# grbl-shield-easydriver.net
KiCad netlist of a schematic drawn in EAGLE
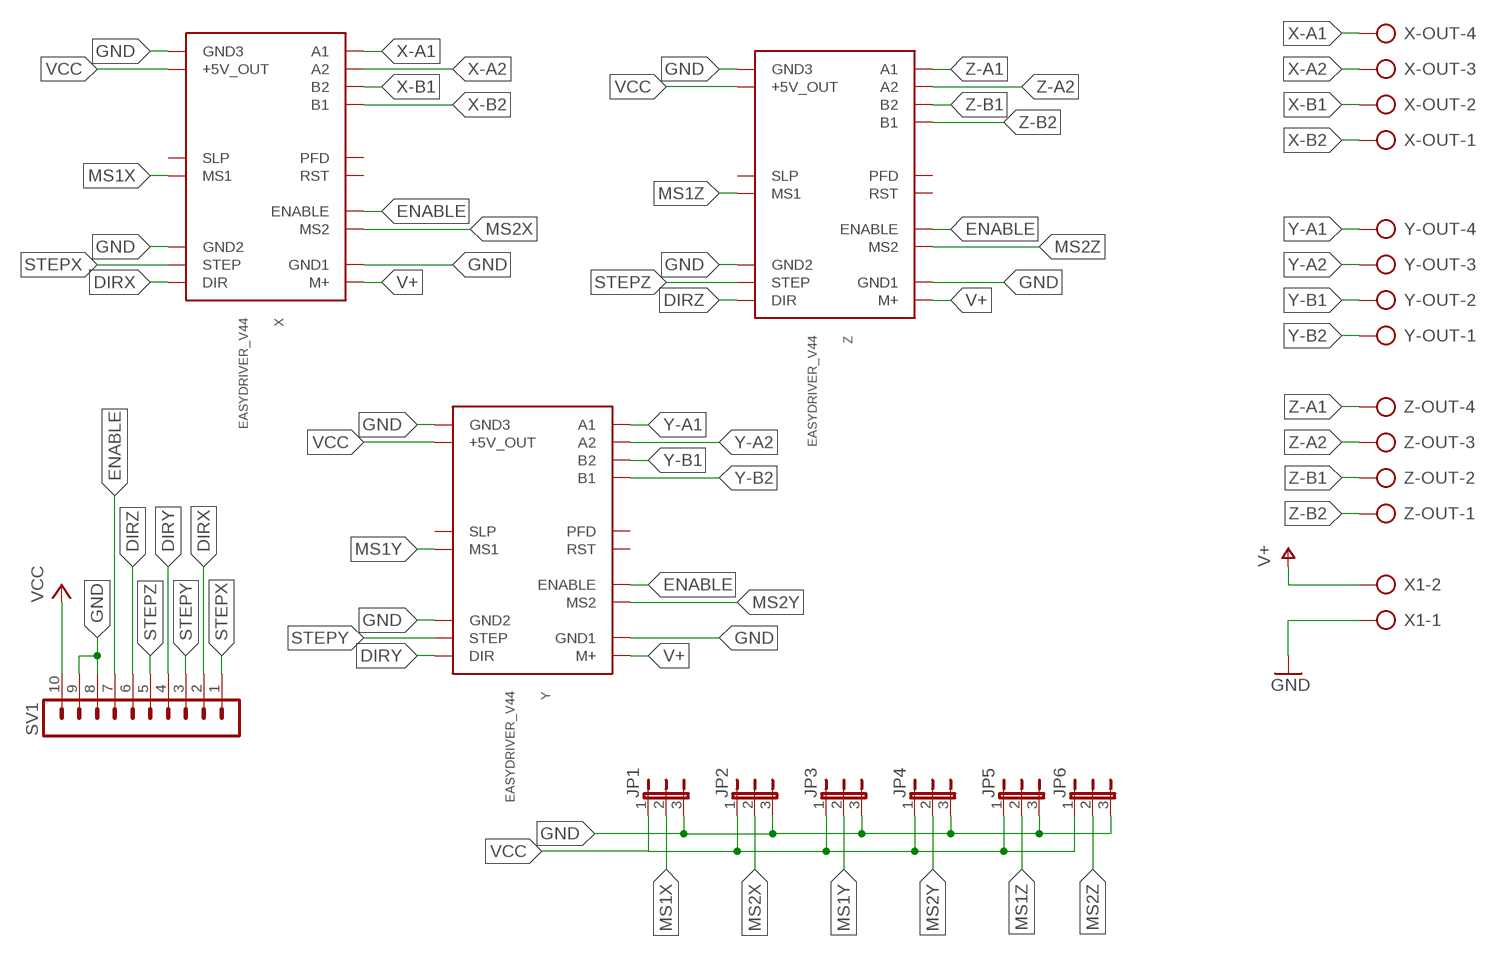
[diagram p0: schematic, sheet 1]

(export (version "E")
  (design (tool "Eeschema 10.0.6"))
  (components
    (comp (ref "JP1")
      (value "JP2E")
      (footprint "eagle-import:JP2")
      (libsource (lib "eagle-import") (part "JP2E"))
    )
    (comp (ref "JP2")
      (value "JP2E")
      (footprint "eagle-import:JP2")
      (libsource (lib "eagle-import") (part "JP2E"))
    )
    (comp (ref "JP3")
      (value "JP2E")
      (footprint "eagle-import:JP2")
      (libsource (lib "eagle-import") (part "JP2E"))
    )
    (comp (ref "JP4")
      (value "JP2E")
      (footprint "eagle-import:JP2")
      (libsource (lib "eagle-import") (part "JP2E"))
    )
    (comp (ref "JP5")
      (value "JP2E")
      (footprint "eagle-import:JP2")
      (libsource (lib "eagle-import") (part "JP2E"))
    )
    (comp (ref "JP6")
      (value "JP2E")
      (footprint "eagle-import:JP2")
      (libsource (lib "eagle-import") (part "JP2E"))
    )
    (comp (ref "SV1")
      (value "MA10-1")
      (footprint "eagle-import:MA10-1")
      (libsource (lib "eagle-import") (part "MA10-1"))
    )
    (comp (ref "X")
      (value "EASYDRIVER_V44")
      (footprint "eagle-import:EASYDRIVER_V44")
      (libsource (lib "eagle-import") (part "EASYDRIVER_V44"))
    )
    (comp (ref "X-OUT")
      (value "AK500/4")
      (footprint "eagle-import:AK500_4")
      (libsource (lib "eagle-import") (part "AK500/4"))
    )
    (comp (ref "X1")
      (value "AK500/2")
      (footprint "eagle-import:AK500_2")
      (libsource (lib "eagle-import") (part "AK500/2"))
    )
    (comp (ref "Y")
      (value "EASYDRIVER_V44")
      (footprint "eagle-import:EASYDRIVER_V44")
      (libsource (lib "eagle-import") (part "EASYDRIVER_V44"))
    )
    (comp (ref "Y-OUT")
      (value "AK500/4")
      (footprint "eagle-import:AK500_4")
      (libsource (lib "eagle-import") (part "AK500/4"))
    )
    (comp (ref "Z")
      (value "EASYDRIVER_V44")
      (footprint "eagle-import:EASYDRIVER_V44")
      (libsource (lib "eagle-import") (part "EASYDRIVER_V44"))
    )
    (comp (ref "Z-OUT")
      (value "AK500/4")
      (footprint "eagle-import:AK500_4")
      (libsource (lib "eagle-import") (part "AK500/4"))
    )
  )
  (nets
    (net (code "1") (name "DIRX") (class "Default")
      (node (ref "SV1") (pin "2") (pinfunction "2_2") (pintype "passive"))
      (node (ref "X") (pin "DIR") (pinfunction "DIR_DIR") (pintype "bidirectional"))
    )
    (net (code "2") (name "DIRY") (class "Default")
      (node (ref "SV1") (pin "4") (pinfunction "4_4") (pintype "passive"))
      (node (ref "Y") (pin "DIR") (pinfunction "DIR_DIR") (pintype "bidirectional"))
    )
    (net (code "3") (name "DIRZ") (class "Default")
      (node (ref "SV1") (pin "6") (pinfunction "6_6") (pintype "passive"))
      (node (ref "Z") (pin "DIR") (pinfunction "DIR_DIR") (pintype "bidirectional"))
    )
    (net (code "4") (name "ENABLE") (class "Default")
      (node (ref "SV1") (pin "7") (pinfunction "7_7") (pintype "passive"))
      (node (ref "X") (pin "ENABLE") (pinfunction "ENABLE_ENABLE") (pintype "bidirectional"))
      (node (ref "Y") (pin "ENABLE") (pinfunction "ENABLE_ENABLE") (pintype "bidirectional"))
      (node (ref "Z") (pin "ENABLE") (pinfunction "ENABLE_ENABLE") (pintype "bidirectional"))
    )
    (net (code "5") (name "GND") (class "Default")
      (node (ref "JP1") (pin "3") (pinfunction "3_3") (pintype "passive"))
      (node (ref "JP2") (pin "3") (pinfunction "3_3") (pintype "passive"))
      (node (ref "JP3") (pin "3") (pinfunction "3_3") (pintype "passive"))
      (node (ref "JP4") (pin "3") (pinfunction "3_3") (pintype "passive"))
      (node (ref "JP5") (pin "3") (pinfunction "3_3") (pintype "passive"))
      (node (ref "JP6") (pin "3") (pinfunction "3_3") (pintype "passive"))
      (node (ref "SV1") (pin "8") (pinfunction "8_8") (pintype "passive"))
      (node (ref "SV1") (pin "9") (pinfunction "9_9") (pintype "passive"))
      (node (ref "X") (pin "GND1") (pinfunction "GND1_GND1") (pintype "bidirectional"))
      (node (ref "X") (pin "GND2") (pinfunction "GND2_GND2") (pintype "bidirectional"))
      (node (ref "X") (pin "GND3") (pinfunction "GND3_GND3") (pintype "bidirectional"))
      (node (ref "X1") (pin "1") (pinfunction "KL_1") (pintype "passive"))
      (node (ref "Y") (pin "GND1") (pinfunction "GND1_GND1") (pintype "bidirectional"))
      (node (ref "Y") (pin "GND2") (pinfunction "GND2_GND2") (pintype "bidirectional"))
      (node (ref "Y") (pin "GND3") (pinfunction "GND3_GND3") (pintype "bidirectional"))
      (node (ref "Z") (pin "GND1") (pinfunction "GND1_GND1") (pintype "bidirectional"))
      (node (ref "Z") (pin "GND2") (pinfunction "GND2_GND2") (pintype "bidirectional"))
      (node (ref "Z") (pin "GND3") (pinfunction "GND3_GND3") (pintype "bidirectional"))
    )
    (net (code "6") (name "MS1X") (class "Default")
      (node (ref "JP1") (pin "2") (pinfunction "2_2") (pintype "passive"))
      (node (ref "X") (pin "MS1") (pinfunction "MS1_MS1") (pintype "bidirectional"))
    )
    (net (code "7") (name "MS1Y") (class "Default")
      (node (ref "JP3") (pin "2") (pinfunction "2_2") (pintype "passive"))
      (node (ref "Y") (pin "MS1") (pinfunction "MS1_MS1") (pintype "bidirectional"))
    )
    (net (code "8") (name "MS1Z") (class "Default")
      (node (ref "JP5") (pin "2") (pinfunction "2_2") (pintype "passive"))
      (node (ref "Z") (pin "MS1") (pinfunction "MS1_MS1") (pintype "bidirectional"))
    )
    (net (code "9") (name "MS2X") (class "Default")
      (node (ref "JP2") (pin "2") (pinfunction "2_2") (pintype "passive"))
      (node (ref "X") (pin "MS2") (pinfunction "MS2_MS2") (pintype "bidirectional"))
    )
    (net (code "10") (name "MS2Y") (class "Default")
      (node (ref "JP4") (pin "2") (pinfunction "2_2") (pintype "passive"))
      (node (ref "Y") (pin "MS2") (pinfunction "MS2_MS2") (pintype "bidirectional"))
    )
    (net (code "11") (name "MS2Z") (class "Default")
      (node (ref "JP6") (pin "2") (pinfunction "2_2") (pintype "passive"))
      (node (ref "Z") (pin "MS2") (pinfunction "MS2_MS2") (pintype "bidirectional"))
    )
    (net (code "12") (name "STEPX") (class "Default")
      (node (ref "SV1") (pin "1") (pinfunction "1_1") (pintype "passive"))
      (node (ref "X") (pin "STEP") (pinfunction "STEP_STEP") (pintype "bidirectional"))
    )
    (net (code "13") (name "STEPY") (class "Default")
      (node (ref "SV1") (pin "3") (pinfunction "3_3") (pintype "passive"))
      (node (ref "Y") (pin "STEP") (pinfunction "STEP_STEP") (pintype "bidirectional"))
    )
    (net (code "14") (name "STEPZ") (class "Default")
      (node (ref "SV1") (pin "5") (pinfunction "5_5") (pintype "passive"))
      (node (ref "Z") (pin "STEP") (pinfunction "STEP_STEP") (pintype "bidirectional"))
    )
    (net (code "15") (name "V+") (class "Default")
      (node (ref "X") (pin "M+") (pinfunction "M+_M+") (pintype "bidirectional"))
      (node (ref "X1") (pin "2") (pinfunction "KL_2") (pintype "passive"))
      (node (ref "Y") (pin "M+") (pinfunction "M+_M+") (pintype "bidirectional"))
      (node (ref "Z") (pin "M+") (pinfunction "M+_M+") (pintype "bidirectional"))
    )
    (net (code "16") (name "VCC") (class "Default")
      (node (ref "JP1") (pin "1") (pinfunction "1_1") (pintype "passive"))
      (node (ref "JP2") (pin "1") (pinfunction "1_1") (pintype "passive"))
      (node (ref "JP3") (pin "1") (pinfunction "1_1") (pintype "passive"))
      (node (ref "JP4") (pin "1") (pinfunction "1_1") (pintype "passive"))
      (node (ref "JP5") (pin "1") (pinfunction "1_1") (pintype "passive"))
      (node (ref "JP6") (pin "1") (pinfunction "1_1") (pintype "passive"))
      (node (ref "SV1") (pin "10") (pinfunction "10_10") (pintype "passive"))
      (node (ref "X") (pin "P$11") (pinfunction "+5V_OUT_P$11") (pintype "bidirectional"))
      (node (ref "Y") (pin "P$11") (pinfunction "+5V_OUT_P$11") (pintype "bidirectional"))
      (node (ref "Z") (pin "P$11") (pinfunction "+5V_OUT_P$11") (pintype "bidirectional"))
    )
    (net (code "17") (name "X-A1") (class "Default")
      (node (ref "X") (pin "A1") (pinfunction "A1_A1") (pintype "bidirectional"))
      (node (ref "X-OUT") (pin "4") (pinfunction "KL_4") (pintype "passive"))
    )
    (net (code "18") (name "X-A2") (class "Default")
      (node (ref "X") (pin "A2") (pinfunction "A2_A2") (pintype "bidirectional"))
      (node (ref "X-OUT") (pin "3") (pinfunction "KL_3") (pintype "passive"))
    )
    (net (code "19") (name "X-B1") (class "Default")
      (node (ref "X") (pin "B2") (pinfunction "B2_B2") (pintype "bidirectional"))
      (node (ref "X-OUT") (pin "2") (pinfunction "KL_2") (pintype "passive"))
    )
    (net (code "20") (name "X-B2") (class "Default")
      (node (ref "X") (pin "B1") (pinfunction "B1_B1") (pintype "bidirectional"))
      (node (ref "X-OUT") (pin "1") (pinfunction "KL_1") (pintype "passive"))
    )
    (net (code "21") (name "Y-A1") (class "Default")
      (node (ref "Y") (pin "A1") (pinfunction "A1_A1") (pintype "bidirectional"))
      (node (ref "Y-OUT") (pin "4") (pinfunction "KL_4") (pintype "passive"))
    )
    (net (code "22") (name "Y-A2") (class "Default")
      (node (ref "Y") (pin "A2") (pinfunction "A2_A2") (pintype "bidirectional"))
      (node (ref "Y-OUT") (pin "3") (pinfunction "KL_3") (pintype "passive"))
    )
    (net (code "23") (name "Y-B1") (class "Default")
      (node (ref "Y") (pin "B2") (pinfunction "B2_B2") (pintype "bidirectional"))
      (node (ref "Y-OUT") (pin "2") (pinfunction "KL_2") (pintype "passive"))
    )
    (net (code "24") (name "Y-B2") (class "Default")
      (node (ref "Y") (pin "B1") (pinfunction "B1_B1") (pintype "bidirectional"))
      (node (ref "Y-OUT") (pin "1") (pinfunction "KL_1") (pintype "passive"))
    )
    (net (code "25") (name "Z-A1") (class "Default")
      (node (ref "Z") (pin "A1") (pinfunction "A1_A1") (pintype "bidirectional"))
      (node (ref "Z-OUT") (pin "4") (pinfunction "KL_4") (pintype "passive"))
    )
    (net (code "26") (name "Z-A2") (class "Default")
      (node (ref "Z") (pin "A2") (pinfunction "A2_A2") (pintype "bidirectional"))
      (node (ref "Z-OUT") (pin "3") (pinfunction "KL_3") (pintype "passive"))
    )
    (net (code "27") (name "Z-B1") (class "Default")
      (node (ref "Z") (pin "B2") (pinfunction "B2_B2") (pintype "bidirectional"))
      (node (ref "Z-OUT") (pin "2") (pinfunction "KL_2") (pintype "passive"))
    )
    (net (code "28") (name "Z-B2") (class "Default")
      (node (ref "Z") (pin "B1") (pinfunction "B1_B1") (pintype "bidirectional"))
      (node (ref "Z-OUT") (pin "1") (pinfunction "KL_1") (pintype "passive"))
    )
    (net (code "29") (name "unconnected-(X-PadPFD)") (class "Default")
      (node (ref "X") (pin "PFD") (pinfunction "PFD_PFD") (pintype "bidirectional"))
    )
    (net (code "30") (name "unconnected-(X-PadRST)") (class "Default")
      (node (ref "X") (pin "RST") (pinfunction "RST_RST") (pintype "bidirectional"))
    )
    (net (code "31") (name "unconnected-(X-SLP-PadSLEEP)") (class "Default")
      (node (ref "X") (pin "SLEEP") (pinfunction "SLP_SLEEP") (pintype "bidirectional"))
    )
    (net (code "32") (name "unconnected-(Y-PadPFD)") (class "Default")
      (node (ref "Y") (pin "PFD") (pinfunction "PFD_PFD") (pintype "bidirectional"))
    )
    (net (code "33") (name "unconnected-(Y-PadRST)") (class "Default")
      (node (ref "Y") (pin "RST") (pinfunction "RST_RST") (pintype "bidirectional"))
    )
    (net (code "34") (name "unconnected-(Y-SLP-PadSLEEP)") (class "Default")
      (node (ref "Y") (pin "SLEEP") (pinfunction "SLP_SLEEP") (pintype "bidirectional"))
    )
    (net (code "35") (name "unconnected-(Z-PadPFD)") (class "Default")
      (node (ref "Z") (pin "PFD") (pinfunction "PFD_PFD") (pintype "bidirectional"))
    )
    (net (code "36") (name "unconnected-(Z-PadRST)") (class "Default")
      (node (ref "Z") (pin "RST") (pinfunction "RST_RST") (pintype "bidirectional"))
    )
    (net (code "37") (name "unconnected-(Z-SLP-PadSLEEP)") (class "Default")
      (node (ref "Z") (pin "SLEEP") (pinfunction "SLP_SLEEP") (pintype "bidirectional"))
    )
  )
)
